# IOIO-OTG.net
KiCad netlist of a schematic drawn in EAGLE
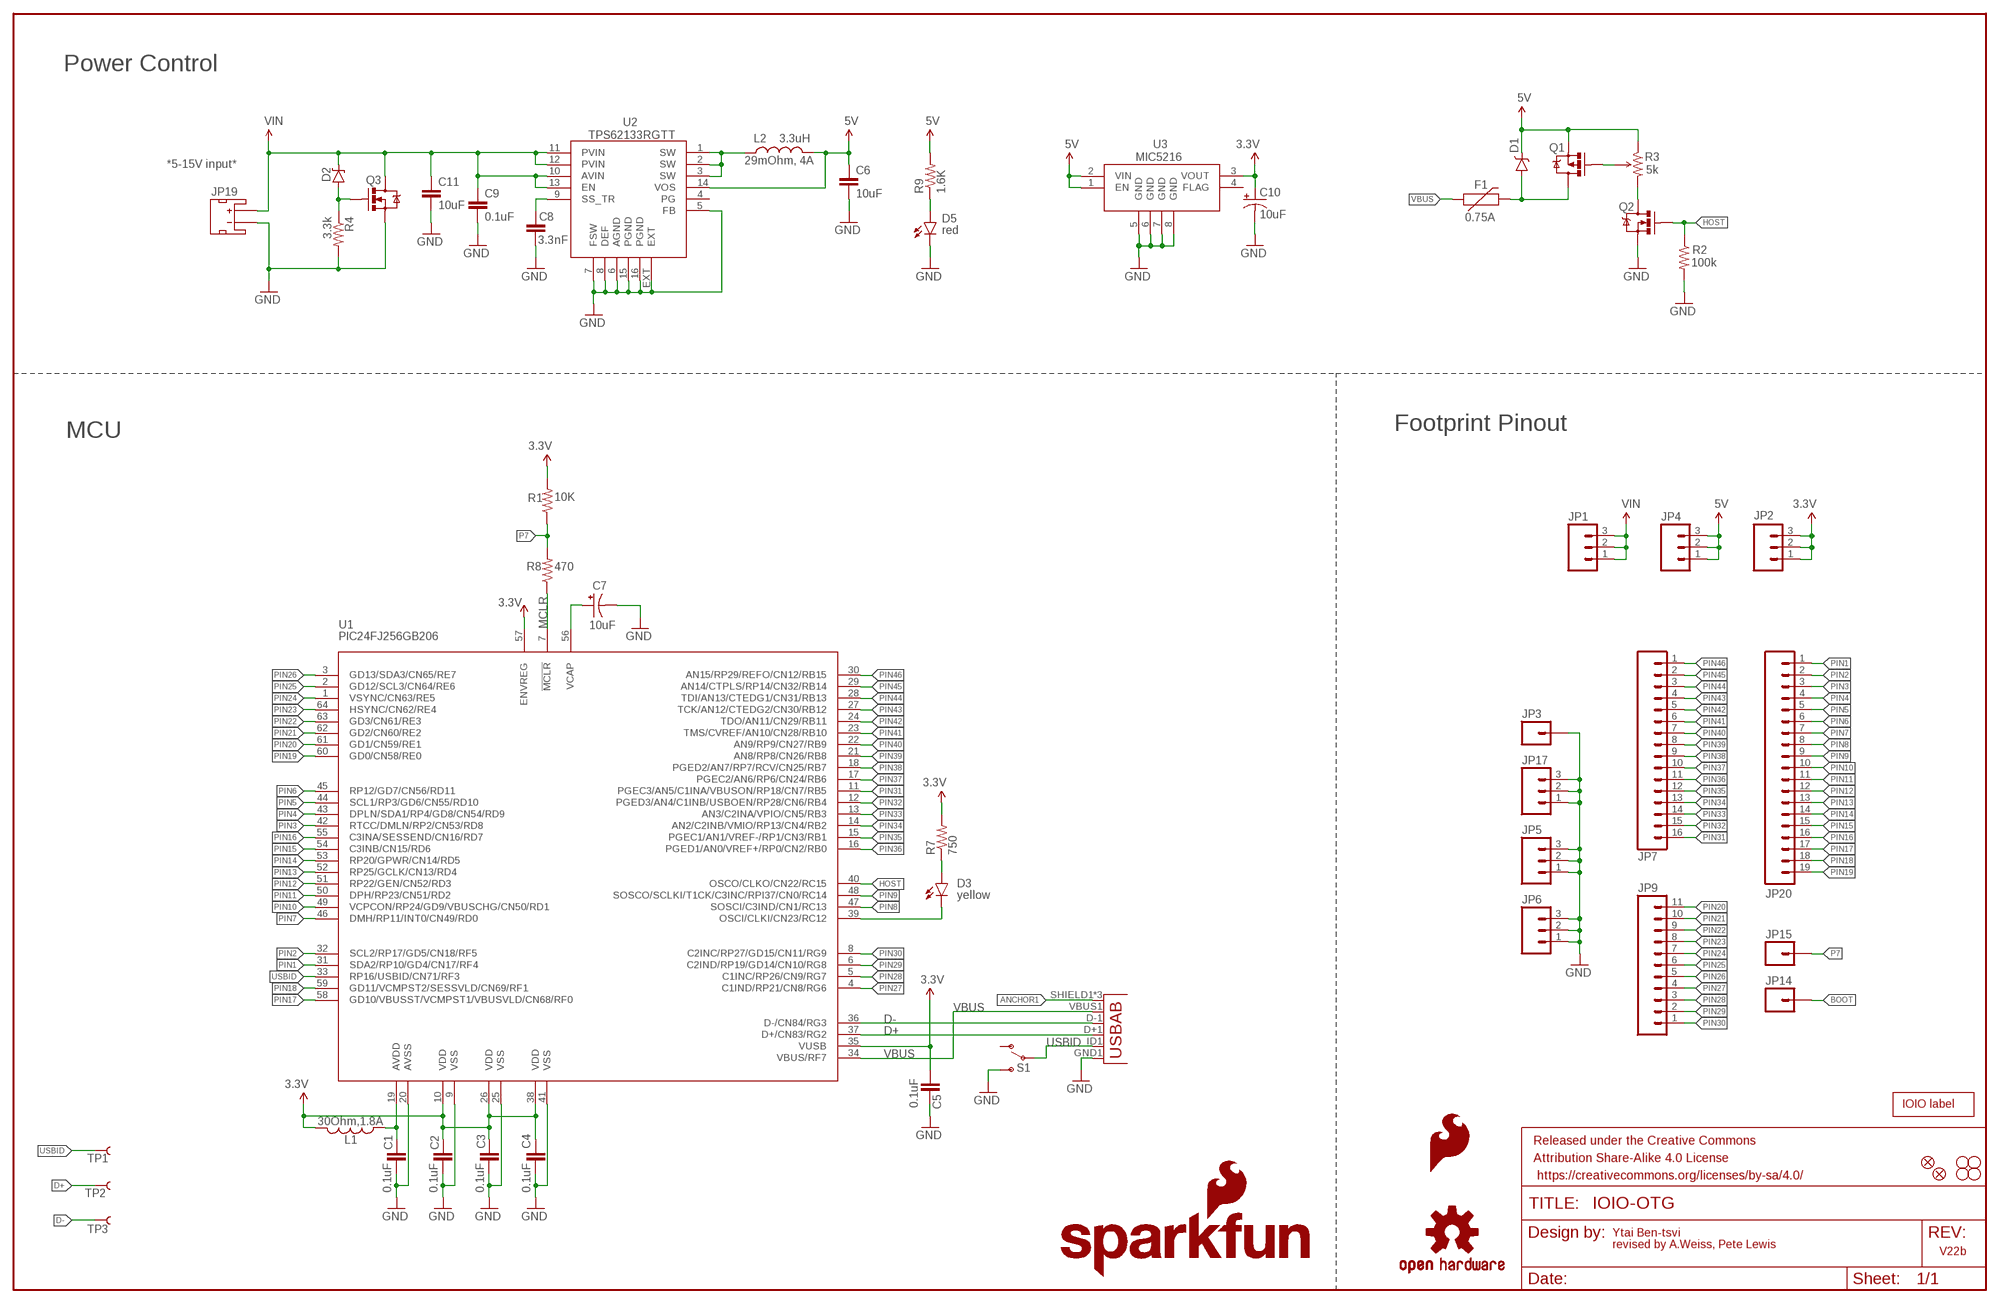
[diagram p0: schematic, sheet 1]

(export (version "E")
  (design (tool "Eeschema 10.0.6"))
  (components
    (comp (ref "C1")
      (value "0.1uF")
      (footprint "eagle-import:0603-CAP")
      (libsource (lib "eagle-import") (part "0.1UF-25V(+80/-20%)(0603)"))
    )
    (comp (ref "C2")
      (value "0.1uF")
      (footprint "eagle-import:0603-CAP")
      (libsource (lib "eagle-import") (part "0.1UF-25V(+80/-20%)(0603)"))
    )
    (comp (ref "C3")
      (value "0.1uF")
      (footprint "eagle-import:0603-CAP")
      (libsource (lib "eagle-import") (part "0.1UF-25V(+80/-20%)(0603)"))
    )
    (comp (ref "C4")
      (value "0.1uF")
      (footprint "eagle-import:0603-CAP")
      (libsource (lib "eagle-import") (part "0.1UF-25V(+80/-20%)(0603)"))
    )
    (comp (ref "C5")
      (value "0.1uF")
      (footprint "eagle-import:0603-CAP")
      (libsource (lib "eagle-import") (part "0.1UF-25V(+80/-20%)(0603)"))
    )
    (comp (ref "C6")
      (value "10uF")
      (footprint "eagle-import:0805-CAP")
      (fields (field (name "PART#") "LMK212BJ106KG-T"))
      (libsource (lib "eagle-import") (part "10UF10V10%(0805)"))
    )
    (comp (ref "C7")
      (value "10uF")
      (footprint "eagle-import:EIA3216")
      (libsource (lib "eagle-import") (part "10UF-16V-10%(TANT)"))
    )
    (comp (ref "C8")
      (value "3.3nF")
      (footprint "eagle-import:0603-CAP")
      (libsource (lib "eagle-import") (part "3.3NF-100V-10%(0603)"))
    )
    (comp (ref "C9")
      (value "0.1uF")
      (footprint "eagle-import:0603-CAP")
      (libsource (lib "eagle-import") (part "0.1UF-25V(+80/-20%)(0603)"))
    )
    (comp (ref "C10")
      (value "10uF")
      (footprint "eagle-import:EIA3216")
      (fields (field (name "PART#") "TAJA106K016RNJ"))
      (libsource (lib "eagle-import") (part "10UF-16V-10%(TANT)"))
    )
    (comp (ref "C11")
      (value "10uF")
      (footprint "eagle-import:1210")
      (fields (field (name "PART#") "UMK325C7106MM-T"))
      (libsource (lib "eagle-import") (part "10UF50V20%(1210)"))
    )
    (comp (ref "D1")
      (value "B340A")
      (footprint "eagle-import:SMA-DIODE")
      (fields (field (name "PART#") "B340A"))
      (libsource (lib "eagle-import") (part "DIODE-SCHOTTKY-B340A"))
    )
    (comp (ref "D2")
      (value "DZ2J160M0L")
      (footprint "eagle-import:PANASONIC_SMINI2-F5-B")
      (fields (field (name "PART#") "DZ2J150M0L"))
      (libsource (lib "eagle-import") (part "DIODE-ZENERDZ2J150M0L"))
    )
    (comp (ref "D3")
      (value "Yellow")
      (footprint "eagle-import:LED-0603")
      (libsource (lib "eagle-import") (part "LED-YELLOW0603-SMART"))
    )
    (comp (ref "D5")
      (value "Red")
      (footprint "eagle-import:LED-0603")
      (libsource (lib "eagle-import") (part "LED-RED0603-SMART"))
    )
    (comp (ref "F1")
      (value "0.75A")
      (footprint "eagle-import:PTC-1206")
      (fields (field (name "PART#") "0ZCA0075FF2G"))
      (libsource (lib "eagle-import") (part "PTCSMD"))
    )
    (comp (ref "FRAME2")
      (value "FRAME-LEDGER")
      (footprint "eagle-import:CREATIVE_COMMONS")
      (libsource (lib "eagle-import") (part "FRAME-LEDGER"))
    )
    (comp (ref "JP1")
      (value "M03PTH")
      (footprint "eagle-import:1X03")
      (libsource (lib "eagle-import") (part "M03PTH"))
    )
    (comp (ref "JP2")
      (value "M03PTH")
      (footprint "eagle-import:1X03")
      (libsource (lib "eagle-import") (part "M03PTH"))
    )
    (comp (ref "JP3")
      (value "M01PTH")
      (footprint "eagle-import:1X01")
      (libsource (lib "eagle-import") (part "M01PTH"))
    )
    (comp (ref "JP4")
      (value "M03PTH")
      (footprint "eagle-import:1X03")
      (libsource (lib "eagle-import") (part "M03PTH"))
    )
    (comp (ref "JP5")
      (value "M03PTH")
      (footprint "eagle-import:1X03")
      (libsource (lib "eagle-import") (part "M03PTH"))
    )
    (comp (ref "JP6")
      (value "M03PTH")
      (footprint "eagle-import:1X03")
      (libsource (lib "eagle-import") (part "M03PTH"))
    )
    (comp (ref "JP7")
      (value "M161X16_NO_SILK")
      (footprint "eagle-import:1X16_NO_SILK")
      (libsource (lib "eagle-import") (part "M161X16_NO_SILK"))
    )
    (comp (ref "JP8")
      (value "FIDUCIALUFIDUCIAL")
      (footprint "eagle-import:MICRO-FIDUCIAL")
      (libsource (lib "eagle-import") (part "FIDUCIALUFIDUCIAL"))
    )
    (comp (ref "JP9")
      (value "M111X11_NO_SILK")
      (footprint "eagle-import:1X11_NO_SILK")
      (libsource (lib "eagle-import") (part "M111X11_NO_SILK"))
    )
    (comp (ref "JP10")
      (value "STAND-OFF")
      (footprint "eagle-import:STAND-OFF")
      (libsource (lib "eagle-import") (part "STAND-OFF"))
    )
    (comp (ref "JP11")
      (value "STAND-OFF")
      (footprint "eagle-import:STAND-OFF")
      (libsource (lib "eagle-import") (part "STAND-OFF"))
    )
    (comp (ref "JP12")
      (value "STAND-OFF")
      (footprint "eagle-import:STAND-OFF")
      (libsource (lib "eagle-import") (part "STAND-OFF"))
    )
    (comp (ref "JP13")
      (value "STAND-OFF")
      (footprint "eagle-import:STAND-OFF")
      (libsource (lib "eagle-import") (part "STAND-OFF"))
    )
    (comp (ref "JP14")
      (value "M01PTH")
      (footprint "eagle-import:1X01")
      (libsource (lib "eagle-import") (part "M01PTH"))
    )
    (comp (ref "JP15")
      (value "M01PTH")
      (footprint "eagle-import:1X01")
      (libsource (lib "eagle-import") (part "M01PTH"))
    )
    (comp (ref "JP16")
      (value "FIDUCIALUFIDUCIAL")
      (footprint "eagle-import:MICRO-FIDUCIAL")
      (libsource (lib "eagle-import") (part "FIDUCIALUFIDUCIAL"))
    )
    (comp (ref "JP17")
      (value "M03PTH")
      (footprint "eagle-import:1X03")
      (libsource (lib "eagle-import") (part "M03PTH"))
    )
    (comp (ref "JP19")
      (value "JST")
      (footprint "eagle-import:JST-2-SMD")
      (libsource (lib "eagle-import") (part "JST_2MM_MALE"))
    )
    (comp (ref "JP20")
      (value "M191X19_NO_SILK")
      (footprint "eagle-import:1X19_NO_SILK")
      (libsource (lib "eagle-import") (part "M191X19_NO_SILK"))
    )
    (comp (ref "JP21")
      (value "AB MICRO USB")
      (footprint "eagle-import:USB-AB-MICRO-SMD_V03")
      (libsource (lib "eagle-import") (part "USB-ABCONN-11794"))
    )
    (comp (ref "L1")
      (value "30Ohm,1.8A")
      (footprint "eagle-import:0603")
      (libsource (lib "eagle-import") (part "INDUCTOR30OHM,1.8A"))
    )
    (comp (ref "L2")
      (value "VLC5045T-3R3N")
      (footprint "eagle-import:CR54")
      (fields (field (name "AM") "3.3uH"))
      (libsource (lib "eagle-import") (part "INDUCTORCR54-3.3UH"))
    )
    (comp (ref "LOGO1")
      (value "OSHW-LOGOS")
      (footprint "eagle-import:OSHW-LOGO-S")
      (libsource (lib "eagle-import") (part "OSHW-LOGOS"))
    )
    (comp (ref "LOGO2")
      (value "SFE_LOGO_NAME_FLAME.1_INCH")
      (footprint "eagle-import:SFE_LOGO_NAME_FLAME_.1")
      (libsource (lib "eagle-import") (part "SFE_LOGO_NAME_FLAME.1_INCH"))
    )
    (comp (ref "LOGO3")
      (value "SFE_LOGO_FLAME.1_INCH")
      (footprint "eagle-import:SFE_LOGO_FLAME_.1")
      (libsource (lib "eagle-import") (part "SFE_LOGO_FLAME.1_INCH"))
    )
    (comp (ref "Q1")
      (value "IRLML2244")
      (footprint "eagle-import:SOT23-3")
      (libsource (lib "eagle-import") (part "MOSFET-PCHANNELIRLML2244"))
    )
    (comp (ref "Q2")
      (value "2N7002PW")
      (footprint "eagle-import:SOT323")
      (fields (field (name "PART#") "2N7002PW"))
      (libsource (lib "eagle-import") (part "MOSFET-NCHANNEL2N7002PW"))
    )
    (comp (ref "Q3")
      (value "MOSFET-NCHANNELAO3404A")
      (footprint "eagle-import:SOT23-3")
      (fields (field (name "PART#") "AO3404A"))
      (libsource (lib "eagle-import") (part "MOSFET-NCHANNELAO3404A"))
    )
    (comp (ref "R1")
      (value "10K")
      (footprint "eagle-import:0603-RES")
      (libsource (lib "eagle-import") (part "10KOHM-1/10W-1%(0603)0603"))
    )
    (comp (ref "R2")
      (value "100k")
      (footprint "eagle-import:0603-RES")
      (libsource (lib "eagle-import") (part "100KOHM-1/10W-1%(0603)"))
    )
    (comp (ref "R3")
      (value "TS53YL502MR10")
      (footprint "eagle-import:TRIMPOT_5MM")
      (fields (field (name "PART#") "TS53YL502MR10"))
      (libsource (lib "eagle-import") (part "TRIMPOTRES-11156"))
    )
    (comp (ref "R4")
      (value "3.3k")
      (footprint "eagle-import:0603-RES")
      (libsource (lib "eagle-import") (part "3.3KOHM1/10W1%(0603)"))
    )
    (comp (ref "R7")
      (value "750")
      (footprint "eagle-import:0603-RES")
      (libsource (lib "eagle-import") (part "750OHM1/10W1%(0603)0603"))
    )
    (comp (ref "R8")
      (value "470")
      (footprint "eagle-import:0603-RES")
      (libsource (lib "eagle-import") (part "470OHM1/10W1%(0603)"))
    )
    (comp (ref "R9")
      (value "1.6K")
      (footprint "eagle-import:0603-RES")
      (libsource (lib "eagle-import") (part "1.6KOHM-1/10W-1%(0603)0603"))
    )
    (comp (ref "S1")
      (value "SWITCH_SPDT")
      (footprint "eagle-import:KPS-1290")
      (libsource (lib "eagle-import") (part "SWITCH_SPDT"))
    )
    (comp (ref "TP1")
      (value "TEST-POINT3")
      (footprint "eagle-import:PAD.03X.03")
      (libsource (lib "eagle-import") (part "TEST-POINT3"))
    )
    (comp (ref "TP2")
      (value "TEST-POINT3")
      (footprint "eagle-import:PAD.03X.03")
      (libsource (lib "eagle-import") (part "TEST-POINT3"))
    )
    (comp (ref "TP3")
      (value "TEST-POINT3")
      (footprint "eagle-import:PAD.03X.03")
      (libsource (lib "eagle-import") (part "TEST-POINT3"))
    )
    (comp (ref "U$6")
      (value "IOIO-OTG")
      (footprint "eagle-import:IOIO-OTG-COPPER-EXPOSED")
      (libsource (lib "eagle-import") (part "IOIO-OTG"))
    )
    (comp (ref "U1")
      (value "PIC24FJ256GB206")
      (footprint "eagle-import:PIC24FXXX_TQFP64")
      (libsource (lib "eagle-import") (part "PIC24FXXXGPX06"))
    )
    (comp (ref "U2")
      (value "TPS62133RGTT")
      (footprint "eagle-import:QFN16-3X3MM_1_1_V03")
      (libsource (lib "eagle-import") (part "TPS62133RGTT{dblquote}{dblquote}"))
    )
    (comp (ref "U3")
      (value "MIC5216")
      (footprint "eagle-import:MSOP8")
      (libsource (lib "eagle-import") (part "V_REG_MIC5216"))
    )
  )
  (nets
    (net (code "1") (name "/MCLR") (class "Default")
      (node (ref "R8") (pin "1") (pinfunction "1_1") (pintype "passive"))
      (node (ref "U1") (pin "7") (pinfunction "~{MCLR}_7") (pintype "input"))
    )
    (net (code "2") (name "3.3V") (class "Default")
      (node (ref "C10") (pin "A") (pinfunction "+_A") (pintype "passive"))
      (node (ref "C2") (pin "1") (pinfunction "1_1") (pintype "passive"))
      (node (ref "C3") (pin "1") (pinfunction "1_1") (pintype "passive"))
      (node (ref "C4") (pin "1") (pinfunction "1_1") (pintype "passive"))
      (node (ref "C5") (pin "1") (pinfunction "1_1") (pintype "passive"))
      (node (ref "JP2") (pin "1") (pinfunction "1_1") (pintype "passive"))
      (node (ref "JP2") (pin "2") (pinfunction "2_2") (pintype "passive"))
      (node (ref "JP2") (pin "3") (pinfunction "3_3") (pintype "passive"))
      (node (ref "L1") (pin "2") (pinfunction "2_2") (pintype "passive"))
      (node (ref "R1") (pin "2") (pinfunction "2_2") (pintype "passive"))
      (node (ref "R7") (pin "2") (pinfunction "2_2") (pintype "passive"))
      (node (ref "U1") (pin "10") (pinfunction "VDD_10") (pintype "power_in"))
      (node (ref "U1") (pin "26") (pinfunction "VDD_26") (pintype "power_in"))
      (node (ref "U1") (pin "35") (pinfunction "VUSB_35") (pintype "power_in"))
      (node (ref "U1") (pin "38") (pinfunction "VDD_38") (pintype "power_in"))
      (node (ref "U1") (pin "57") (pinfunction "ENVREG_57") (pintype "input"))
      (node (ref "U3") (pin "3") (pinfunction "VOUT_3") (pintype "bidirectional"))
    )
    (net (code "3") (name "5V") (class "Default")
      (node (ref "C6") (pin "1") (pinfunction "1_1") (pintype "passive"))
      (node (ref "D1") (pin "C") (pinfunction "C_C") (pintype "passive"))
      (node (ref "JP4") (pin "1") (pinfunction "1_1") (pintype "passive"))
      (node (ref "JP4") (pin "2") (pinfunction "2_2") (pintype "passive"))
      (node (ref "JP4") (pin "3") (pinfunction "3_3") (pintype "passive"))
      (node (ref "L2") (pin "P$2") (pinfunction "2_P$2") (pintype "passive"))
      (node (ref "Q1") (pin "2") (pinfunction "S_2") (pintype "passive"))
      (node (ref "R3") (pin "A") (pinfunction "CCW_A") (pintype "passive"))
      (node (ref "R9") (pin "2") (pinfunction "2_2") (pintype "passive"))
      (node (ref "U2") (pin "14") (pinfunction "VOS_14") (pintype "bidirectional"))
      (node (ref "U3") (pin "1") (pinfunction "EN_1") (pintype "bidirectional"))
      (node (ref "U3") (pin "2") (pinfunction "VIN_2") (pintype "bidirectional"))
    )
    (net (code "4") (name "ANCHOR1") (class "Default")
      (node (ref "JP21") (pin "SHIELD1") (pinfunction "SHIELD_SHIELD1") (pintype "bidirectional"))
      (node (ref "JP21") (pin "SHIELD2") (pinfunction "SHIELD_SHIELD2") (pintype "bidirectional"))
      (node (ref "JP21") (pin "SHIELD3") (pinfunction "SHIELD_SHIELD3") (pintype "bidirectional"))
    )
    (net (code "5") (name "BOOT") (class "Default")
      (node (ref "D3") (pin "C") (pinfunction "C_C") (pintype "passive"))
      (node (ref "JP14") (pin "1") (pinfunction "1_1") (pintype "passive"))
      (node (ref "U1") (pin "39") (pinfunction "OSCI/CLKI/CN23/RC12_39") (pintype "bidirectional"))
    )
    (net (code "6") (name "D+") (class "Default")
      (node (ref "JP21") (pin "D+1") (pinfunction "D+_D+1") (pintype "bidirectional"))
      (node (ref "TP2") (pin "P$1") (pinfunction "1_P$1") (pintype "bidirectional"))
      (node (ref "U1") (pin "37") (pinfunction "D+/CN83/RG2_37") (pintype "bidirectional"))
    )
    (net (code "7") (name "D-") (class "Default")
      (node (ref "JP21") (pin "D-1") (pinfunction "D-_D-1") (pintype "bidirectional"))
      (node (ref "TP3") (pin "P$1") (pinfunction "1_P$1") (pintype "bidirectional"))
      (node (ref "U1") (pin "36") (pinfunction "D-/CN84/RG3_36") (pintype "bidirectional"))
    )
    (net (code "8") (name "GND") (class "Default")
      (node (ref "C1") (pin "2") (pinfunction "2_2") (pintype "passive"))
      (node (ref "C10") (pin "C") (pinfunction "-_C") (pintype "passive"))
      (node (ref "C11") (pin "2") (pinfunction "2_2") (pintype "passive"))
      (node (ref "C2") (pin "2") (pinfunction "2_2") (pintype "passive"))
      (node (ref "C3") (pin "2") (pinfunction "2_2") (pintype "passive"))
      (node (ref "C4") (pin "2") (pinfunction "2_2") (pintype "passive"))
      (node (ref "C5") (pin "2") (pinfunction "2_2") (pintype "passive"))
      (node (ref "C6") (pin "2") (pinfunction "2_2") (pintype "passive"))
      (node (ref "C7") (pin "C") (pinfunction "-_C") (pintype "passive"))
      (node (ref "C8") (pin "2") (pinfunction "2_2") (pintype "passive"))
      (node (ref "C9") (pin "2") (pinfunction "2_2") (pintype "passive"))
      (node (ref "D5") (pin "C") (pinfunction "C_C") (pintype "passive"))
      (node (ref "JP17") (pin "1") (pinfunction "1_1") (pintype "passive"))
      (node (ref "JP17") (pin "2") (pinfunction "2_2") (pintype "passive"))
      (node (ref "JP17") (pin "3") (pinfunction "3_3") (pintype "passive"))
      (node (ref "JP19") (pin "1") (pinfunction "-_1") (pintype "bidirectional"))
      (node (ref "JP21") (pin "GND1") (pinfunction "GND_GND1") (pintype "bidirectional"))
      (node (ref "JP3") (pin "1") (pinfunction "1_1") (pintype "passive"))
      (node (ref "JP5") (pin "1") (pinfunction "1_1") (pintype "passive"))
      (node (ref "JP5") (pin "2") (pinfunction "2_2") (pintype "passive"))
      (node (ref "JP5") (pin "3") (pinfunction "3_3") (pintype "passive"))
      (node (ref "JP6") (pin "1") (pinfunction "1_1") (pintype "passive"))
      (node (ref "JP6") (pin "2") (pinfunction "2_2") (pintype "passive"))
      (node (ref "JP6") (pin "3") (pinfunction "3_3") (pintype "passive"))
      (node (ref "Q2") (pin "2") (pinfunction "S_2") (pintype "passive"))
      (node (ref "Q3") (pin "2") (pinfunction "S_2") (pintype "passive"))
      (node (ref "R2") (pin "2") (pinfunction "2_2") (pintype "passive"))
      (node (ref "R4") (pin "2") (pinfunction "2_2") (pintype "passive"))
      (node (ref "S1") (pin "S") (pinfunction "S_S") (pintype "passive"))
      (node (ref "U1") (pin "20") (pinfunction "AVSS_20") (pintype "power_in"))
      (node (ref "U1") (pin "25") (pinfunction "VSS_25") (pintype "power_in"))
      (node (ref "U1") (pin "41") (pinfunction "VSS_41") (pintype "power_in"))
      (node (ref "U1") (pin "9") (pinfunction "VSS_9") (pintype "power_in"))
      (node (ref "U2") (pin "15") (pinfunction "PGND_15") (pintype "bidirectional"))
      (node (ref "U2") (pin "16") (pinfunction "PGND_16") (pintype "bidirectional"))
      (node (ref "U2") (pin "5") (pinfunction "FB_5") (pintype "bidirectional"))
      (node (ref "U2") (pin "6") (pinfunction "AGND_6") (pintype "bidirectional"))
      (node (ref "U2") (pin "7") (pinfunction "FSW_7") (pintype "bidirectional"))
      (node (ref "U2") (pin "8") (pinfunction "DEF_8") (pintype "bidirectional"))
      (node (ref "U2") (pin "EXT") (pinfunction "EXT_EXT") (pintype "bidirectional"))
      (node (ref "U3") (pin "5") (pinfunction "GND_5") (pintype "bidirectional"))
      (node (ref "U3") (pin "6") (pinfunction "GND_6") (pintype "bidirectional"))
      (node (ref "U3") (pin "7") (pinfunction "GND_7") (pintype "bidirectional"))
      (node (ref "U3") (pin "8") (pinfunction "GND_8") (pintype "bidirectional"))
    )
    (net (code "9") (name "HOST") (class "Default")
      (node (ref "Q2") (pin "1") (pinfunction "G_1") (pintype "passive"))
      (node (ref "R2") (pin "1") (pinfunction "1_1") (pintype "passive"))
      (node (ref "U1") (pin "40") (pinfunction "OSCO/CLKO/CN22/RC15_40") (pintype "bidirectional"))
    )
    (net (code "10") (name "Net-(C7-+)") (class "Default")
      (node (ref "C7") (pin "A") (pinfunction "+_A") (pintype "passive"))
      (node (ref "U1") (pin "56") (pinfunction "VCAP_56") (pintype "power_in"))
    )
    (net (code "11") (name "Net-(D3-PadA)") (class "Default")
      (node (ref "D3") (pin "A") (pinfunction "A_A") (pintype "passive"))
      (node (ref "R7") (pin "1") (pinfunction "1_1") (pintype "passive"))
    )
    (net (code "12") (name "Net-(D5-PadA)") (class "Default")
      (node (ref "D5") (pin "A") (pinfunction "A_A") (pintype "passive"))
      (node (ref "R9") (pin "1") (pinfunction "1_1") (pintype "passive"))
    )
    (net (code "13") (name "Net-(L2-1)") (class "Default")
      (node (ref "L2") (pin "P$1") (pinfunction "1_P$1") (pintype "passive"))
      (node (ref "U2") (pin "1") (pinfunction "SW_1") (pintype "bidirectional"))
      (node (ref "U2") (pin "2") (pinfunction "SW_2") (pintype "bidirectional"))
      (node (ref "U2") (pin "3") (pinfunction "SW_3") (pintype "bidirectional"))
    )
    (net (code "14") (name "Net-(Q1-D)") (class "Default")
      (node (ref "D1") (pin "A") (pinfunction "A_A") (pintype "passive"))
      (node (ref "F1") (pin "2") (pinfunction "2_2") (pintype "bidirectional"))
      (node (ref "Q1") (pin "3") (pinfunction "D_3") (pintype "passive"))
    )
    (net (code "15") (name "Net-(Q1-G)") (class "Default")
      (node (ref "Q1") (pin "1") (pinfunction "G_1") (pintype "passive"))
      (node (ref "R3") (pin "B") (pinfunction "WIPER_B") (pintype "passive"))
    )
    (net (code "16") (name "Net-(Q2-D)") (class "Default")
      (node (ref "Q2") (pin "3") (pinfunction "D_3") (pintype "passive"))
      (node (ref "R3") (pin "C") (pinfunction "CW_C") (pintype "passive"))
    )
    (net (code "17") (name "Net-(Q3-G)") (class "Default")
      (node (ref "D2") (pin "A") (pinfunction "A_A") (pintype "passive"))
      (node (ref "Q3") (pin "1") (pinfunction "G_1") (pintype "passive"))
      (node (ref "R4") (pin "1") (pinfunction "1_1") (pintype "passive"))
    )
    (net (code "18") (name "Net-(U1-AVDD)") (class "Default")
      (node (ref "C1") (pin "1") (pinfunction "1_1") (pintype "passive"))
      (node (ref "L1") (pin "1") (pinfunction "1_1") (pintype "passive"))
      (node (ref "U1") (pin "19") (pinfunction "AVDD_19") (pintype "power_in"))
    )
    (net (code "19") (name "Net-(U2-SS_TR)") (class "Default")
      (node (ref "C8") (pin "1") (pinfunction "1_1") (pintype "passive"))
      (node (ref "U2") (pin "9") (pinfunction "SS_TR_9") (pintype "bidirectional"))
    )
    (net (code "20") (name "P7") (class "Default")
      (node (ref "JP15") (pin "1") (pinfunction "1_1") (pintype "passive"))
      (node (ref "R1") (pin "1") (pinfunction "1_1") (pintype "passive"))
      (node (ref "R8") (pin "2") (pinfunction "2_2") (pintype "passive"))
    )
    (net (code "21") (name "PIN1") (class "Default")
      (node (ref "JP20") (pin "1") (pinfunction "1_1") (pintype "passive"))
      (node (ref "U1") (pin "31") (pinfunction "SDA2/RP10/GD4/CN17/RF4_31") (pintype "bidirectional"))
    )
    (net (code "22") (name "PIN2") (class "Default")
      (node (ref "JP20") (pin "2") (pinfunction "2_2") (pintype "passive"))
      (node (ref "U1") (pin "32") (pinfunction "SCL2/RP17/GD5/CN18/RF5_32") (pintype "bidirectional"))
    )
    (net (code "23") (name "PIN3") (class "Default")
      (node (ref "JP20") (pin "3") (pinfunction "3_3") (pintype "passive"))
      (node (ref "U1") (pin "42") (pinfunction "RTCC/DMLN/RP2/CN53/RD8_42") (pintype "bidirectional"))
    )
    (net (code "24") (name "PIN4") (class "Default")
      (node (ref "JP20") (pin "4") (pinfunction "4_4") (pintype "passive"))
      (node (ref "U1") (pin "43") (pinfunction "DPLN/SDA1/RP4/GD8/CN54/RD9_43") (pintype "bidirectional"))
    )
    (net (code "25") (name "PIN5") (class "Default")
      (node (ref "JP20") (pin "5") (pinfunction "5_5") (pintype "passive"))
      (node (ref "U1") (pin "44") (pinfunction "SCL1/RP3/GD6/CN55/RD10_44") (pintype "bidirectional"))
    )
    (net (code "26") (name "PIN6") (class "Default")
      (node (ref "JP20") (pin "6") (pinfunction "6_6") (pintype "passive"))
      (node (ref "U1") (pin "45") (pinfunction "RP12/GD7/CN56/RD11_45") (pintype "bidirectional"))
    )
    (net (code "27") (name "PIN7") (class "Default")
      (node (ref "JP20") (pin "7") (pinfunction "7_7") (pintype "passive"))
      (node (ref "U1") (pin "46") (pinfunction "DMH/RP11/INT0/CN49/RD0_46") (pintype "bidirectional"))
    )
    (net (code "28") (name "PIN8") (class "Default")
      (node (ref "JP20") (pin "8") (pinfunction "8_8") (pintype "passive"))
      (node (ref "U1") (pin "47") (pinfunction "SOSCI/C3IND/CN1/RC13_47") (pintype "bidirectional"))
    )
    (net (code "29") (name "PIN9") (class "Default")
      (node (ref "JP20") (pin "9") (pinfunction "9_9") (pintype "passive"))
      (node (ref "U1") (pin "48") (pinfunction "SOSCO/SCLKI/T1CK/C3INC/RPI37/CN0/RC14_48") (pintype "bidirectional"))
    )
    (net (code "30") (name "PIN10") (class "Default")
      (node (ref "JP20") (pin "10") (pinfunction "10_10") (pintype "passive"))
      (node (ref "U1") (pin "49") (pinfunction "VCPCON/RP24/GD9/VBUSCHG/CN50/RD1_49") (pintype "bidirectional"))
    )
    (net (code "31") (name "PIN11") (class "Default")
      (node (ref "JP20") (pin "11") (pinfunction "11_11") (pintype "passive"))
      (node (ref "U1") (pin "50") (pinfunction "DPH/RP23/CN51/RD2_50") (pintype "bidirectional"))
    )
    (net (code "32") (name "PIN12") (class "Default")
      (node (ref "JP20") (pin "12") (pinfunction "12_12") (pintype "passive"))
      (node (ref "U1") (pin "51") (pinfunction "RP22/GEN/CN52/RD3_51") (pintype "bidirectional"))
    )
    (net (code "33") (name "PIN13") (class "Default")
      (node (ref "JP20") (pin "13") (pinfunction "13_13") (pintype "passive"))
      (node (ref "U1") (pin "52") (pinfunction "RP25/GCLK/CN13/RD4_52") (pintype "bidirectional"))
    )
    (net (code "34") (name "PIN14") (class "Default")
      (node (ref "JP20") (pin "14") (pinfunction "14_14") (pintype "passive"))
      (node (ref "U1") (pin "53") (pinfunction "RP20/GPWR/CN14/RD5_53") (pintype "bidirectional"))
    )
    (net (code "35") (name "PIN15") (class "Default")
      (node (ref "JP20") (pin "15") (pinfunction "15_15") (pintype "passive"))
      (node (ref "U1") (pin "54") (pinfunction "C3INB/CN15/RD6_54") (pintype "bidirectional"))
    )
    (net (code "36") (name "PIN16") (class "Default")
      (node (ref "JP20") (pin "16") (pinfunction "16_16") (pintype "passive"))
      (node (ref "U1") (pin "55") (pinfunction "C3INA/SESSEND/CN16/RD7_55") (pintype "bidirectional"))
    )
    (net (code "37") (name "PIN17") (class "Default")
      (node (ref "JP20") (pin "17") (pinfunction "17_17") (pintype "passive"))
      (node (ref "U1") (pin "58") (pinfunction "GD10/VBUSST/VCMPST1/VBUSVLD/CN68/RF0_58") (pintype "bidirectional"))
    )
    (net (code "38") (name "PIN18") (class "Default")
      (node (ref "JP20") (pin "18") (pinfunction "18_18") (pintype "passive"))
      (node (ref "U1") (pin "59") (pinfunction "GD11/VCMPST2/SESSVLD/CN69/RF1_59") (pintype "bidirectional"))
    )
    (net (code "39") (name "PIN19") (class "Default")
      (node (ref "JP20") (pin "19") (pinfunction "19_19") (pintype "passive"))
      (node (ref "U1") (pin "60") (pinfunction "GD0/CN58/RE0_60") (pintype "bidirectional"))
    )
    (net (code "40") (name "PIN20") (class "Default")
      (node (ref "JP9") (pin "11") (pinfunction "11_11") (pintype "passive"))
      (node (ref "U1") (pin "61") (pinfunction "GD1/CN59/RE1_61") (pintype "bidirectional"))
    )
    (net (code "41") (name "PIN21") (class "Default")
      (node (ref "JP9") (pin "10") (pinfunction "10_10") (pintype "passive"))
      (node (ref "U1") (pin "62") (pinfunction "GD2/CN60/RE2_62") (pintype "bidirectional"))
    )
    (net (code "42") (name "PIN22") (class "Default")
      (node (ref "JP9") (pin "9") (pinfunction "9_9") (pintype "passive"))
      (node (ref "U1") (pin "63") (pinfunction "GD3/CN61/RE3_63") (pintype "bidirectional"))
    )
    (net (code "43") (name "PIN23") (class "Default")
      (node (ref "JP9") (pin "8") (pinfunction "8_8") (pintype "passive"))
      (node (ref "U1") (pin "64") (pinfunction "HSYNC/CN62/RE4_64") (pintype "bidirectional"))
    )
    (net (code "44") (name "PIN24") (class "Default")
      (node (ref "JP9") (pin "7") (pinfunction "7_7") (pintype "passive"))
      (node (ref "U1") (pin "1") (pinfunction "VSYNC/CN63/RE5_1") (pintype "bidirectional"))
    )
    (net (code "45") (name "PIN25") (class "Default")
      (node (ref "JP9") (pin "6") (pinfunction "6_6") (pintype "passive"))
      (node (ref "U1") (pin "2") (pinfunction "GD12/SCL3/CN64/RE6_2") (pintype "bidirectional"))
    )
    (net (code "46") (name "PIN26") (class "Default")
      (node (ref "JP9") (pin "5") (pinfunction "5_5") (pintype "passive"))
      (node (ref "U1") (pin "3") (pinfunction "GD13/SDA3/CN65/RE7_3") (pintype "bidirectional"))
    )
    (net (code "47") (name "PIN27") (class "Default")
      (node (ref "JP9") (pin "4") (pinfunction "4_4") (pintype "passive"))
      (node (ref "U1") (pin "4") (pinfunction "C1IND/RP21/CN8/RG6_4") (pintype "bidirectional"))
    )
    (net (code "48") (name "PIN28") (class "Default")
      (node (ref "JP9") (pin "3") (pinfunction "3_3") (pintype "passive"))
      (node (ref "U1") (pin "5") (pinfunction "C1INC/RP26/CN9/RG7_5") (pintype "bidirectional"))
    )
    (net (code "49") (name "PIN29") (class "Default")
      (node (ref "JP9") (pin "2") (pinfunction "2_2") (pintype "passive"))
      (node (ref "U1") (pin "6") (pinfunction "C2IND/RP19/GD14/CN10/RG8_6") (pintype "bidirectional"))
    )
    (net (code "50") (name "PIN30") (class "Default")
      (node (ref "JP9") (pin "1") (pinfunction "1_1") (pintype "passive"))
      (node (ref "U1") (pin "8") (pinfunction "C2INC/RP27/GD15/CN11/RG9_8") (pintype "bidirectional"))
    )
    (net (code "51") (name "PIN31") (class "Default")
      (node (ref "JP7") (pin "16") (pinfunction "16_16") (pintype "passive"))
      (node (ref "U1") (pin "11") (pinfunction "PGEC3/AN5/C1INA/VBUSON/RP18/CN7/RB5_11") (pintype "bidirectional"))
    )
    (net (code "52") (name "PIN32") (class "Default")
      (node (ref "JP7") (pin "15") (pinfunction "15_15") (pintype "passive"))
      (node (ref "U1") (pin "12") (pinfunction "PGED3/AN4/C1INB/USBOEN/RP28/CN6/RB4_12") (pintype "bidirectional"))
    )
    (net (code "53") (name "PIN33") (class "Default")
      (node (ref "JP7") (pin "14") (pinfunction "14_14") (pintype "passive"))
      (node (ref "U1") (pin "13") (pinfunction "AN3/C2INA/VPIO/CN5/RB3_13") (pintype "bidirectional"))
    )
    (net (code "54") (name "PIN34") (class "Default")
      (node (ref "JP7") (pin "13") (pinfunction "13_13") (pintype "passive"))
      (node (ref "U1") (pin "14") (pinfunction "AN2/C2INB/VMIO/RP13/CN4/RB2_14") (pintype "bidirectional"))
    )
    (net (code "55") (name "PIN35") (class "Default")
      (node (ref "JP7") (pin "12") (pinfunction "12_12") (pintype "passive"))
      (node (ref "U1") (pin "15") (pinfunction "PGEC1/AN1/VREF-/RP1/CN3/RB1_15") (pintype "bidirectional"))
    )
    (net (code "56") (name "PIN36") (class "Default")
      (node (ref "JP7") (pin "11") (pinfunction "11_11") (pintype "passive"))
      (node (ref "U1") (pin "16") (pinfunction "PGED1/AN0/VREF+/RP0/CN2/RB0_16") (pintype "bidirectional"))
    )
    (net (code "57") (name "PIN37") (class "Default")
      (node (ref "JP7") (pin "10") (pinfunction "10_10") (pintype "passive"))
      (node (ref "U1") (pin "17") (pinfunction "PGEC2/AN6/RP6/CN24/RB6_17") (pintype "bidirectional"))
    )
    (net (code "58") (name "PIN38") (class "Default")
      (node (ref "JP7") (pin "9") (pinfunction "9_9") (pintype "passive"))
      (node (ref "U1") (pin "18") (pinfunction "PGED2/AN7/RP7/RCV/CN25/RB7_18") (pintype "bidirectional"))
    )
    (net (code "59") (name "PIN39") (class "Default")
      (node (ref "JP7") (pin "8") (pinfunction "8_8") (pintype "passive"))
      (node (ref "U1") (pin "21") (pinfunction "AN8/RP8/CN26/RB8_21") (pintype "bidirectional"))
    )
    (net (code "60") (name "PIN40") (class "Default")
      (node (ref "JP7") (pin "7") (pinfunction "7_7") (pintype "passive"))
      (node (ref "U1") (pin "22") (pinfunction "AN9/RP9/CN27/RB9_22") (pintype "bidirectional"))
    )
    (net (code "61") (name "PIN41") (class "Default")
      (node (ref "JP7") (pin "6") (pinfunction "6_6") (pintype "passive"))
      (node (ref "U1") (pin "23") (pinfunction "TMS/CVREF/AN10/CN28/RB10_23") (pintype "bidirectional"))
    )
    (net (code "62") (name "PIN42") (class "Default")
      (node (ref "JP7") (pin "5") (pinfunction "5_5") (pintype "passive"))
      (node (ref "U1") (pin "24") (pinfunction "TDO/AN11/CN29/RB11_24") (pintype "bidirectional"))
    )
    (net (code "63") (name "PIN43") (class "Default")
      (node (ref "JP7") (pin "4") (pinfunction "4_4") (pintype "passive"))
      (node (ref "U1") (pin "27") (pinfunction "TCK/AN12/CTEDG2/CN30/RB12_27") (pintype "bidirectional"))
    )
    (net (code "64") (name "PIN44") (class "Default")
      (node (ref "JP7") (pin "3") (pinfunction "3_3") (pintype "passive"))
      (node (ref "U1") (pin "28") (pinfunction "TDI/AN13/CTEDG1/CN31/RB13_28") (pintype "bidirectional"))
    )
    (net (code "65") (name "PIN45") (class "Default")
      (node (ref "JP7") (pin "2") (pinfunction "2_2") (pintype "passive"))
      (node (ref "U1") (pin "29") (pinfunction "AN14/CTPLS/RP14/CN32/RB14_29") (pintype "bidirectional"))
    )
    (net (code "66") (name "PIN46") (class "Default")
      (node (ref "JP7") (pin "1") (pinfunction "1_1") (pintype "passive"))
      (node (ref "U1") (pin "30") (pinfunction "AN15/RP29/REFO/CN12/RB15_30") (pintype "bidirectional"))
    )
    (net (code "67") (name "USBID") (class "Default")
      (node (ref "JP21") (pin "ID1") (pinfunction "USBID_ID1") (pintype "bidirectional"))
      (node (ref "S1") (pin "P") (pinfunction "P_P") (pintype "passive"))
      (node (ref "TP1") (pin "P$1") (pinfunction "1_P$1") (pintype "bidirectional"))
      (node (ref "U1") (pin "33") (pinfunction "RP16/USBID/CN71/RF3_33") (pintype "bidirectional"))
    )
    (net (code "68") (name "VBUS") (class "Default")
      (node (ref "F1") (pin "1") (pinfunction "1_1") (pintype "bidirectional"))
      (node (ref "JP21") (pin "VBUS1") (pinfunction "VBUS_VBUS1") (pintype "bidirectional"))
      (node (ref "U1") (pin "34") (pinfunction "VBUS/RF7_34") (pintype "input"))
    )
    (net (code "69") (name "VIN") (class "Default")
      (node (ref "C11") (pin "1") (pinfunction "1_1") (pintype "passive"))
      (node (ref "C9") (pin "1") (pinfunction "1_1") (pintype "passive"))
      (node (ref "D2") (pin "C") (pinfunction "C_C") (pintype "passive"))
      (node (ref "JP1") (pin "1") (pinfunction "1_1") (pintype "passive"))
      (node (ref "JP1") (pin "2") (pinfunction "2_2") (pintype "passive"))
      (node (ref "JP1") (pin "3") (pinfunction "3_3") (pintype "passive"))
      (node (ref "JP19") (pin "2") (pinfunction "+_2") (pintype "bidirectional"))
      (node (ref "Q3") (pin "3") (pinfunction "D_3") (pintype "passive"))
      (node (ref "U2") (pin "10") (pinfunction "AVIN_10") (pintype "bidirectional"))
      (node (ref "U2") (pin "11") (pinfunction "PVIN_11") (pintype "bidirectional"))
      (node (ref "U2") (pin "12") (pinfunction "PVIN_12") (pintype "bidirectional"))
      (node (ref "U2") (pin "13") (pinfunction "EN_13") (pintype "bidirectional"))
    )
    (net (code "70") (name "unconnected-(JP19-PAD1-PadNC1)") (class "Default")
      (node (ref "JP19") (pin "NC1") (pinfunction "PAD1_NC1") (pintype "bidirectional"))
    )
    (net (code "71") (name "unconnected-(JP19-PAD2-PadNC2)") (class "Default")
      (node (ref "JP19") (pin "NC2") (pinfunction "PAD2_NC2") (pintype "bidirectional"))
    )
    (net (code "72") (name "unconnected-(S1-PadO)") (class "Default")
      (node (ref "S1") (pin "O") (pinfunction "O_O") (pintype "passive"))
    )
    (net (code "73") (name "unconnected-(U2-PG-Pad4)") (class "Default")
      (node (ref "U2") (pin "4") (pinfunction "PG_4") (pintype "bidirectional"))
    )
    (net (code "74") (name "unconnected-(U3-FLAG-Pad4)") (class "Default")
      (node (ref "U3") (pin "4") (pinfunction "FLAG_4") (pintype "bidirectional"))
    )
  )
)
